# SAMV71_Xplained_Ultra_Connectors.net
KiCad netlist of a schematic drawn in Altium Designer
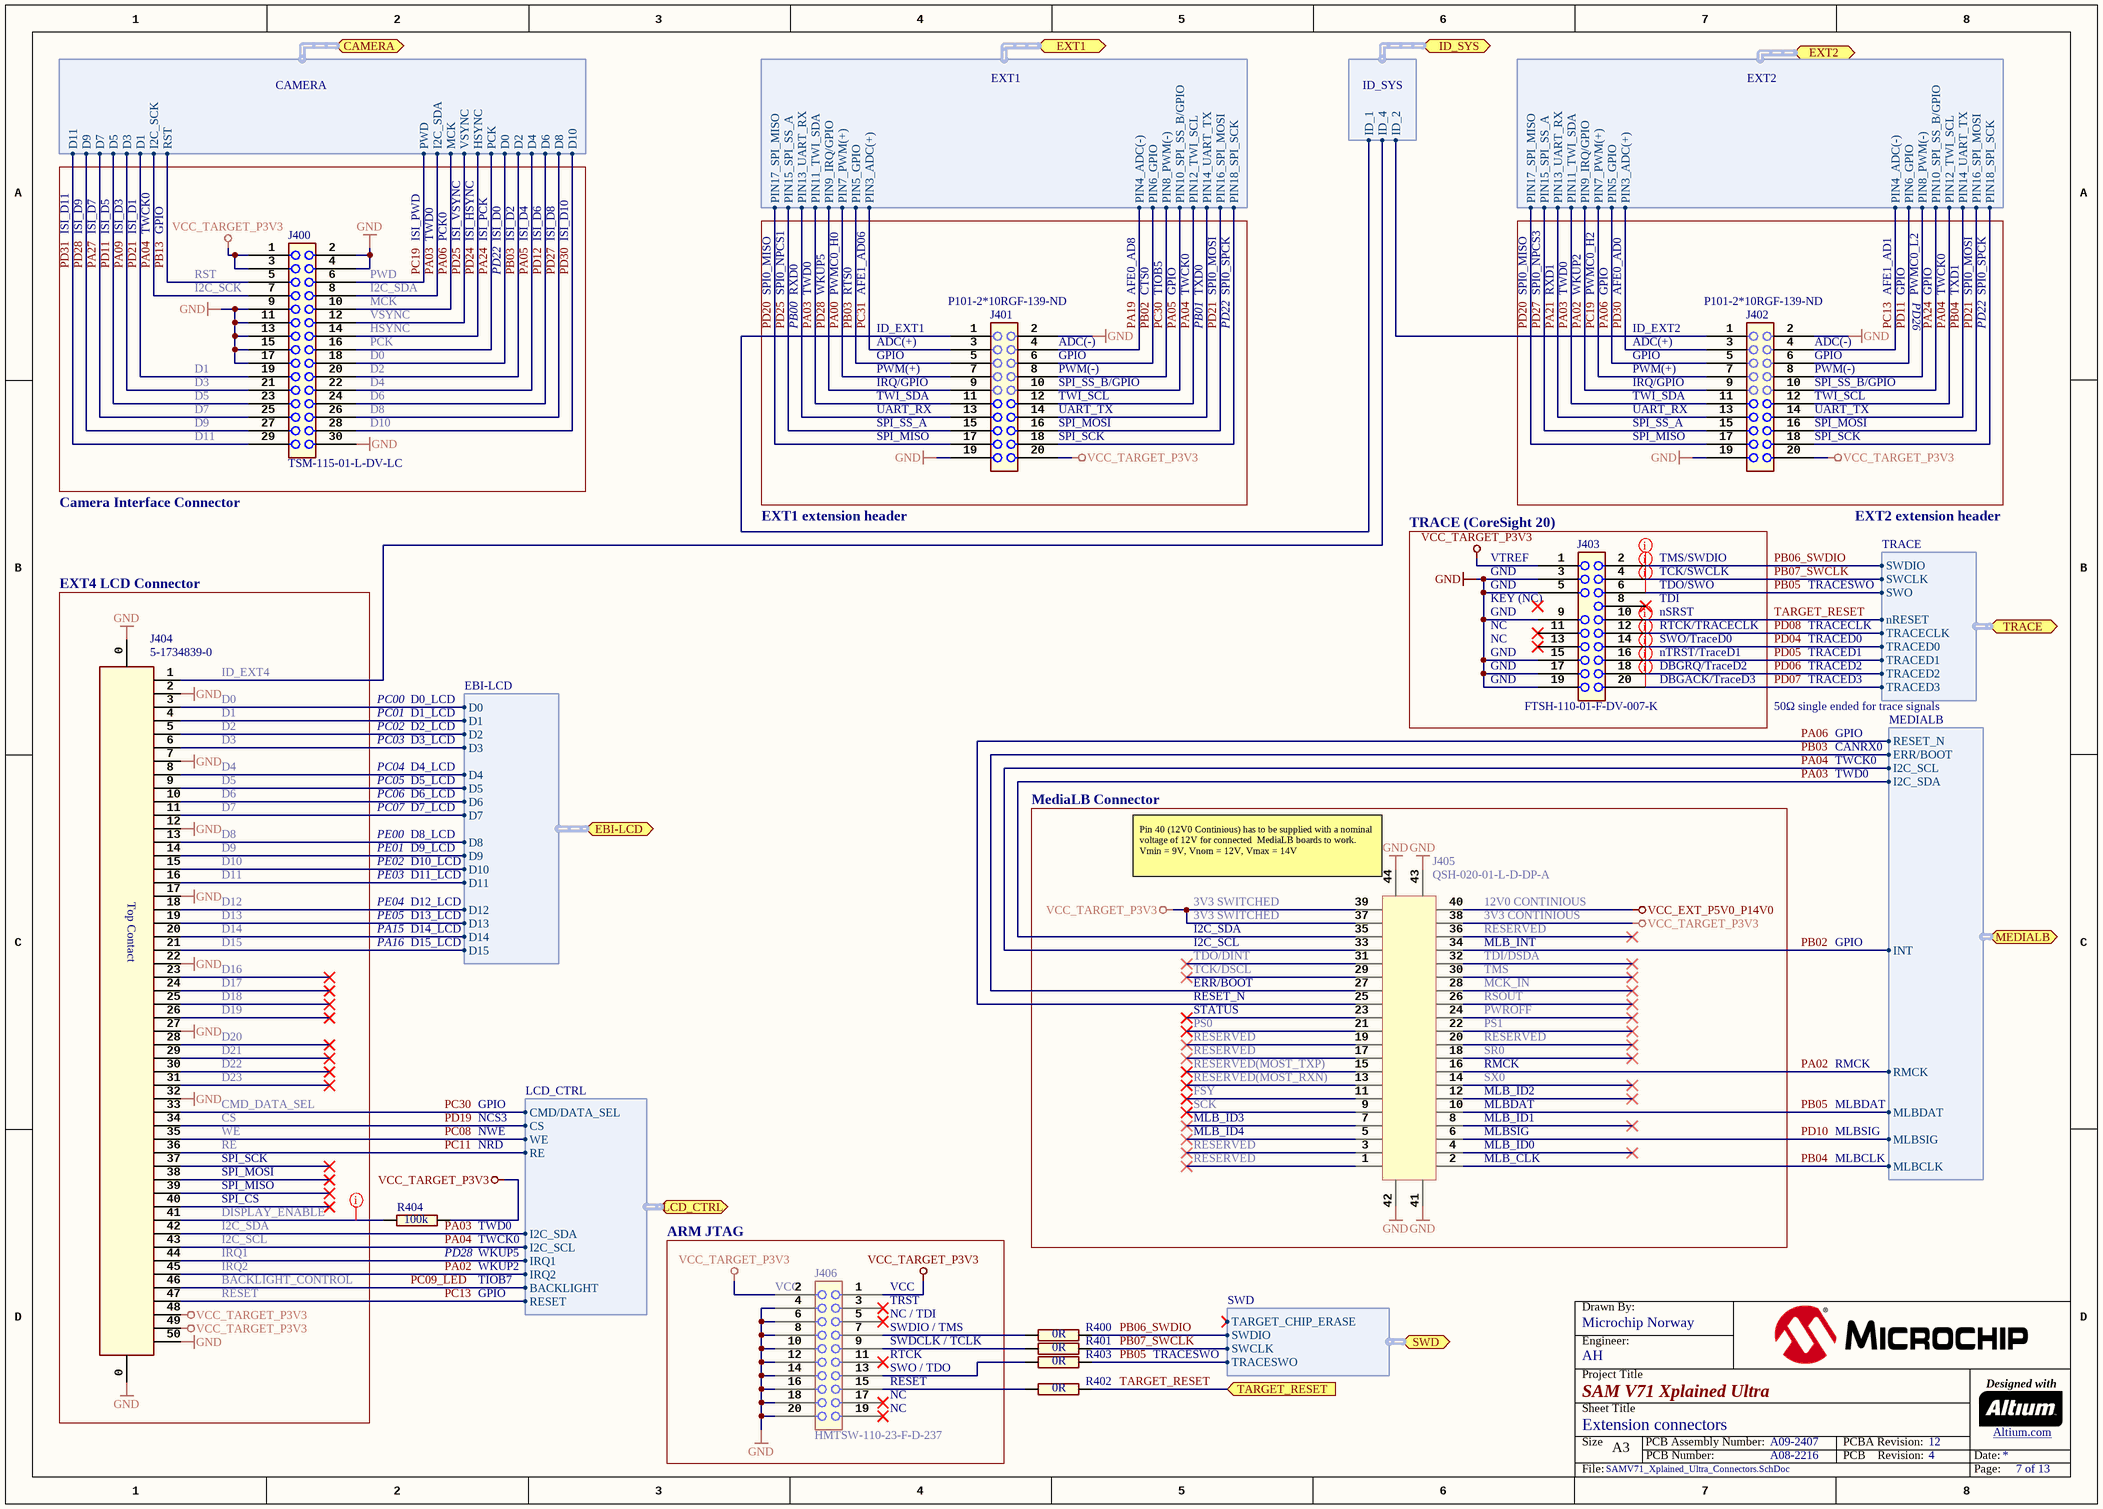
[diagram p0: SAMV71_Xplained_Ultra_Connectors.SchDoc]

(export (version "E")
  (design (tool "Eeschema 10.0.6"))
  (components
    (comp (ref "J400")
      (value "TSM-115-01-L-DV-LC")
      (footprint "AP8-00884")
      (description "Samtec TSM series, 2x15 pin header, straight, 2.54mm pitch SMD, locking leads.")
      (fields (field (name "MANUFACTURER") "SAMTEC"))
      (libsource (lib "AltiumDbLib") (part "HEADER 2x15"))
    )
    (comp (ref "J401")
      (value "P101-2*10RGF-139-ND")
      (footprint "AP8-00622")
      (description "Pin header, 2x10, Right Angle, 2.54mm, THM, Pin In Paste")
      (fields (field (name "MANUFACTURER") "Pro-data International Corp"))
      (libsource (lib "AltiumDbLib") (part "HEADER 2x10"))
    )
    (comp (ref "J402")
      (value "P101-2*10RGF-139-ND")
      (footprint "AP8-00622")
      (description "Pin header, 2x10, Right Angle, 2.54mm, THM, Pin In Paste")
      (fields (field (name "MANUFACTURER") "Pro-data International Corp"))
      (libsource (lib "AltiumDbLib") (part "HEADER 2x10"))
    )
    (comp (ref "J403")
      (value "FTSH-110-01-F-DV-007-K")
      (footprint "AP8-00910")
      (description "SAMTEC FTSH series 50-mil header, shrouded, pin 7 removed, SMD")
      (fields (field (name "MANUFACTURER") "SAMTEC"))
      (libsource (lib "AltiumDbLib") (part "FTSH-110-01-F-DV-007-K"))
    )
    (comp (ref "J404")
      (value "5-1734839-0")
      (footprint "AP8-00774")
      (description "50 pin FPC connector, e=0.5mm, single side contact (top).")
      (fields (field (name "MANUFACTURER") "TE Connectivity"))
      (libsource (lib "AltiumDbLib") (part "5-1734839-0"))
    )
    (comp (ref "J405")
      (value "QSH-020-01-L-D-DP-A")
      (footprint "AP8-00878")
      (description "SAMTEC 0.5mm, 20-pair, High-Speed Differential Pair Socket")
      (fields
        (field (name "MANUFACTURER") "SAMTEC")
        (field (name "Comment") "For SMSC MediaLB, \r\nMates with QTH-020-01-X-D-DP-XXX")
      )
      (libsource (lib "AltiumDbLib") (part "QSH-020-01-L-D-DP-A"))
    )
    (comp (ref "J406")
      (value "HMTSW-110-23-F-D-237")
      (footprint "AP8-00744")
      (description "2x10 pin header, 2.54mm pitch, Pin-in-Paste THM, 1mm hole")
      (fields (field (name "MANUFACTURER") "SAMTEC"))
      (libsource (lib "AltiumDbLib") (part "HEADER 2x10"))
    )
    (comp (ref "R400")
      (value "0R")
      (footprint "AP2-00000")
      (description "RES 0.0 OHM 1/16W 0402 SMD")
      (fields (field (name "TOLERANCE") "1 %") (field (name "MANUFACTURER") "(n/a)"))
      (libsource (lib "AltiumDbLib") (part "R2"))
    )
    (comp (ref "R401")
      (value "0R")
      (footprint "AP2-00000")
      (description "RES 0.0 OHM 1/16W 0402 SMD")
      (fields (field (name "TOLERANCE") "1 %") (field (name "MANUFACTURER") "(n/a)"))
      (libsource (lib "AltiumDbLib") (part "R2"))
    )
    (comp (ref "R402")
      (value "0R")
      (footprint "AP2-00000")
      (description "RES 0.0 OHM 1/16W 0402 SMD")
      (fields (field (name "TOLERANCE") "1 %") (field (name "MANUFACTURER") "(n/a)"))
      (libsource (lib "AltiumDbLib") (part "R2"))
    )
    (comp (ref "R403")
      (value "0R")
      (footprint "AP2-00000")
      (description "RES 0.0 OHM 1/16W 0402 SMD")
      (fields (field (name "TOLERANCE") "1 %") (field (name "MANUFACTURER") "(n/a)"))
      (libsource (lib "AltiumDbLib") (part "R2"))
    )
    (comp (ref "R404")
      (value "100k")
      (footprint "AP2-00011")
      (description "Thick film resistor, SMD 0402, 1/16W, 1%")
      (fields (field (name "TOLERANCE") "1 %") (field (name "MANUFACTURER") "ASJ"))
      (libsource (lib "") (part "R2_1"))
    )
  )
  (nets
    (net (code "10") (name "/D12") (class "Default")
      (node (ref "J404") (pin "18") (pinfunction "18_18") (pintype "passive"))
    )
    (net (code "11") (name "/D13") (class "Default")
      (node (ref "J404") (pin "19") (pinfunction "19_19") (pintype "passive"))
    )
    (net (code "12") (name "/D14") (class "Default")
      (node (ref "J404") (pin "20") (pinfunction "20_20") (pintype "passive"))
    )
    (net (code "13") (name "/D15") (class "Default")
      (node (ref "J404") (pin "21") (pinfunction "21_21") (pintype "passive"))
    )
    (net (code "14") (name "/ID_1") (class "Default")
      (node (ref "J401") (pin "1") (pinfunction "1_1") (pintype "passive"))
    )
    (net (code "15") (name "/ID_2") (class "Default")
      (node (ref "J402") (pin "1") (pinfunction "1_1") (pintype "passive"))
    )
    (net (code "16") (name "/ID_4") (class "Default")
      (node (ref "J404") (pin "1") (pinfunction "1_1") (pintype "passive"))
    )
    (net (code "17") (name "/IRQ1") (class "Default")
      (node (ref "J404") (pin "44") (pinfunction "44_44") (pintype "passive"))
    )
    (net (code "18") (name "/PA00") (class "Default")
      (node (ref "J401") (pin "7") (pinfunction "7_7") (pintype "passive"))
    )
    (net (code "19") (name "/PA02") (class "Default")
      (node (ref "J402") (pin "9") (pinfunction "9_9") (pintype "passive"))
      (node (ref "J404") (pin "45") (pinfunction "45_45") (pintype "passive"))
      (node (ref "J405") (pin "16") (pinfunction "16_16") (pintype "passive"))
    )
    (net (code "20") (name "/PA03") (class "Default")
      (node (ref "J400") (pin "8") (pinfunction "8_8") (pintype "passive"))
      (node (ref "J401") (pin "11") (pinfunction "11_11") (pintype "passive"))
      (node (ref "J402") (pin "11") (pinfunction "11_11") (pintype "passive"))
      (node (ref "J404") (pin "42") (pinfunction "42_42") (pintype "passive"))
      (node (ref "J405") (pin "35") (pinfunction "35_35") (pintype "passive"))
    )
    (net (code "21") (name "/PA04") (class "Default")
      (node (ref "J400") (pin "7") (pinfunction "7_7") (pintype "passive"))
      (node (ref "J401") (pin "12") (pinfunction "12_12") (pintype "passive"))
      (node (ref "J402") (pin "12") (pinfunction "12_12") (pintype "passive"))
      (node (ref "J404") (pin "43") (pinfunction "43_43") (pintype "passive"))
      (node (ref "J405") (pin "33") (pinfunction "33_33") (pintype "passive"))
    )
    (net (code "22") (name "/PA05") (class "Default")
      (node (ref "J400") (pin "22") (pinfunction "22_22") (pintype "passive"))
      (node (ref "J401") (pin "10") (pinfunction "10_10") (pintype "passive"))
    )
    (net (code "23") (name "/PA06") (class "Default")
      (node (ref "J400") (pin "10") (pinfunction "10_10") (pintype "passive"))
      (node (ref "J402") (pin "5") (pinfunction "5_5") (pintype "passive"))
      (node (ref "J405") (pin "25") (pinfunction "25_25") (pintype "passive"))
    )
    (net (code "24") (name "/PA09") (class "Default")
      (node (ref "J400") (pin "21") (pinfunction "21_21") (pintype "passive"))
    )
    (net (code "25") (name "/PA19") (class "Default")
      (node (ref "J401") (pin "4") (pinfunction "4_4") (pintype "passive"))
    )
    (net (code "26") (name "/PA21") (class "Default")
      (node (ref "J402") (pin "13") (pinfunction "13_13") (pintype "passive"))
    )
    (net (code "27") (name "/PA24") (class "Default")
      (node (ref "J400") (pin "16") (pinfunction "16_16") (pintype "passive"))
      (node (ref "J402") (pin "10") (pinfunction "10_10") (pintype "passive"))
    )
    (net (code "28") (name "/PA27") (class "Default")
      (node (ref "J400") (pin "25") (pinfunction "25_25") (pintype "passive"))
    )
    (net (code "29") (name "/PB02") (class "Default")
      (node (ref "J401") (pin "6") (pinfunction "6_6") (pintype "passive"))
      (node (ref "J405") (pin "34") (pinfunction "34_34") (pintype "passive"))
    )
    (net (code "30") (name "/PB03") (class "Default")
      (node (ref "J400") (pin "20") (pinfunction "20_20") (pintype "passive"))
      (node (ref "J401") (pin "5") (pinfunction "5_5") (pintype "passive"))
      (node (ref "J405") (pin "27") (pinfunction "27_27") (pintype "passive"))
    )
    (net (code "31") (name "/PB04") (class "Default")
      (node (ref "J402") (pin "14") (pinfunction "14_14") (pintype "passive"))
      (node (ref "J405") (pin "2") (pinfunction "2_2") (pintype "passive"))
    )
    (net (code "32") (name "/PB05") (class "Default")
      (node (ref "J403") (pin "6") (pinfunction "6_6") (pintype "passive"))
      (node (ref "J405") (pin "10") (pinfunction "10_10") (pintype "passive"))
      (node (ref "R403") (pin "2") (pinfunction "2_2") (pintype "passive"))
    )
    (net (code "33") (name "/PB06_SWDIO") (class "Default")
      (node (ref "J403") (pin "2") (pinfunction "2_2") (pintype "passive"))
      (node (ref "R400") (pin "2") (pinfunction "2_2") (pintype "passive"))
    )
    (net (code "34") (name "/PB07_SWCLK") (class "Default")
      (node (ref "J403") (pin "4") (pinfunction "4_4") (pintype "passive"))
      (node (ref "R401") (pin "2") (pinfunction "2_2") (pintype "passive"))
    )
    (net (code "35") (name "/PB13") (class "Default")
      (node (ref "J400") (pin "5") (pinfunction "5_5") (pintype "passive"))
    )
    (net (code "36") (name "/PC08") (class "Default")
      (node (ref "J404") (pin "35") (pinfunction "35_35") (pintype "passive"))
    )
    (net (code "37") (name "/PC09_LED") (class "Default")
      (node (ref "J404") (pin "46") (pinfunction "46_46") (pintype "passive"))
    )
    (net (code "38") (name "/PC11") (class "Default")
      (node (ref "J404") (pin "36") (pinfunction "36_36") (pintype "passive"))
    )
    (net (code "39") (name "/PC13") (class "Default")
      (node (ref "J402") (pin "4") (pinfunction "4_4") (pintype "passive"))
      (node (ref "J404") (pin "47") (pinfunction "47_47") (pintype "passive"))
    )
    (net (code "40") (name "/PC19") (class "Default")
      (node (ref "J400") (pin "6") (pinfunction "6_6") (pintype "passive"))
      (node (ref "J402") (pin "7") (pinfunction "7_7") (pintype "passive"))
    )
    (net (code "41") (name "/PC30") (class "Default")
      (node (ref "J401") (pin "8") (pinfunction "8_8") (pintype "passive"))
      (node (ref "J404") (pin "33") (pinfunction "33_33") (pintype "passive"))
    )
    (net (code "42") (name "/PC31") (class "Default")
      (node (ref "J401") (pin "3") (pinfunction "3_3") (pintype "passive"))
    )
    (net (code "43") (name "/PD04") (class "Default")
      (node (ref "J403") (pin "14") (pinfunction "14_14") (pintype "passive"))
    )
    (net (code "44") (name "/PD05") (class "Default")
      (node (ref "J403") (pin "16") (pinfunction "16_16") (pintype "passive"))
    )
    (net (code "45") (name "/PD06") (class "Default")
      (node (ref "J403") (pin "18") (pinfunction "18_18") (pintype "passive"))
    )
    (net (code "46") (name "/PD07") (class "Default")
      (node (ref "J403") (pin "20") (pinfunction "20_20") (pintype "passive"))
    )
    (net (code "47") (name "/PD08") (class "Default")
      (node (ref "J403") (pin "12") (pinfunction "12_12") (pintype "passive"))
    )
    (net (code "48") (name "/PD10") (class "Default")
      (node (ref "J405") (pin "6") (pinfunction "6_6") (pintype "passive"))
    )
    (net (code "49") (name "/PD11") (class "Default")
      (node (ref "J400") (pin "23") (pinfunction "23_23") (pintype "passive"))
      (node (ref "J402") (pin "6") (pinfunction "6_6") (pintype "passive"))
    )
    (net (code "50") (name "/PD12") (class "Default")
      (node (ref "J400") (pin "24") (pinfunction "24_24") (pintype "passive"))
    )
    (net (code "51") (name "/PD19") (class "Default")
      (node (ref "J404") (pin "34") (pinfunction "34_34") (pintype "passive"))
    )
    (net (code "52") (name "/PD20") (class "Default")
      (node (ref "J401") (pin "17") (pinfunction "17_17") (pintype "passive"))
      (node (ref "J402") (pin "17") (pinfunction "17_17") (pintype "passive"))
    )
    (net (code "53") (name "/PD21") (class "Default")
      (node (ref "J400") (pin "19") (pinfunction "19_19") (pintype "passive"))
      (node (ref "J401") (pin "16") (pinfunction "16_16") (pintype "passive"))
      (node (ref "J402") (pin "16") (pinfunction "16_16") (pintype "passive"))
    )
    (net (code "54") (name "/PD24") (class "Default")
      (node (ref "J400") (pin "14") (pinfunction "14_14") (pintype "passive"))
    )
    (net (code "55") (name "/PD25") (class "Default")
      (node (ref "J400") (pin "12") (pinfunction "12_12") (pintype "passive"))
      (node (ref "J401") (pin "15") (pinfunction "15_15") (pintype "passive"))
    )
    (net (code "56") (name "/PD27") (class "Default")
      (node (ref "J400") (pin "26") (pinfunction "26_26") (pintype "passive"))
      (node (ref "J402") (pin "15") (pinfunction "15_15") (pintype "passive"))
    )
    (net (code "57") (name "/PD28") (class "Default")
      (node (ref "J400") (pin "27") (pinfunction "27_27") (pintype "passive"))
      (node (ref "J401") (pin "9") (pinfunction "9_9") (pintype "passive"))
    )
    (net (code "58") (name "/PD30") (class "Default")
      (node (ref "J400") (pin "28") (pinfunction "28_28") (pintype "passive"))
      (node (ref "J402") (pin "3") (pinfunction "3_3") (pintype "passive"))
    )
    (net (code "59") (name "/PD31") (class "Default")
      (node (ref "J400") (pin "29") (pinfunction "29_29") (pintype "passive"))
    )
    (net (code "60") (name "/TARGET_RESET") (class "Default")
      (node (ref "J403") (pin "10") (pinfunction "10_10") (pintype "passive"))
      (node (ref "R402") (pin "2") (pinfunction "2_2") (pintype "passive"))
    )
    (net (code "70") (name "GND") (class "Default")
      (node (ref "J400") (pin "11") (pinfunction "11_11") (pintype "passive"))
      (node (ref "J400") (pin "13") (pinfunction "13_13") (pintype "passive"))
      (node (ref "J400") (pin "15") (pinfunction "15_15") (pintype "passive"))
      (node (ref "J400") (pin "17") (pinfunction "17_17") (pintype "passive"))
      (node (ref "J400") (pin "2") (pinfunction "2_2") (pintype "passive"))
      (node (ref "J400") (pin "30") (pinfunction "30_30") (pintype "passive"))
      (node (ref "J400") (pin "4") (pinfunction "4_4") (pintype "passive"))
      (node (ref "J400") (pin "9") (pinfunction "9_9") (pintype "passive"))
      (node (ref "J401") (pin "19") (pinfunction "19_19") (pintype "passive"))
      (node (ref "J401") (pin "2") (pinfunction "2_2") (pintype "passive"))
      (node (ref "J402") (pin "19") (pinfunction "19_19") (pintype "passive"))
      (node (ref "J402") (pin "2") (pinfunction "2_2") (pintype "passive"))
      (node (ref "J403") (pin "15") (pinfunction "15_15") (pintype "passive"))
      (node (ref "J403") (pin "17") (pinfunction "17_17") (pintype "passive"))
      (node (ref "J403") (pin "19") (pinfunction "19_19") (pintype "passive"))
      (node (ref "J403") (pin "3") (pinfunction "3_3") (pintype "passive"))
      (node (ref "J403") (pin "5") (pinfunction "5_5") (pintype "passive"))
      (node (ref "J403") (pin "9") (pinfunction "9_9") (pintype "passive"))
      (node (ref "J404") (pin "0") (pinfunction "1_0") (pintype "passive"))
      (node (ref "J404") (pin "12") (pinfunction "12_12") (pintype "passive"))
      (node (ref "J404") (pin "17") (pinfunction "17_17") (pintype "passive"))
      (node (ref "J404") (pin "2") (pinfunction "2_2") (pintype "passive"))
      (node (ref "J404") (pin "22") (pinfunction "22_22") (pintype "passive"))
      (node (ref "J404") (pin "27") (pinfunction "27_27") (pintype "passive"))
      (node (ref "J404") (pin "32") (pinfunction "32_32") (pintype "passive"))
      (node (ref "J404") (pin "50") (pinfunction "50_50") (pintype "passive"))
      (node (ref "J404") (pin "7") (pinfunction "7_7") (pintype "passive"))
      (node (ref "J405") (pin "41") (pinfunction "41_41") (pintype "passive"))
      (node (ref "J405") (pin "42") (pinfunction "42_42") (pintype "passive"))
      (node (ref "J405") (pin "43") (pinfunction "43_43") (pintype "passive"))
      (node (ref "J405") (pin "44") (pinfunction "44_44") (pintype "passive"))
      (node (ref "J406") (pin "10") (pinfunction "10_10") (pintype "passive"))
      (node (ref "J406") (pin "12") (pinfunction "12_12") (pintype "passive"))
      (node (ref "J406") (pin "14") (pinfunction "14_14") (pintype "passive"))
      (node (ref "J406") (pin "16") (pinfunction "16_16") (pintype "passive"))
      (node (ref "J406") (pin "18") (pinfunction "18_18") (pintype "passive"))
      (node (ref "J406") (pin "20") (pinfunction "20_20") (pintype "passive"))
      (node (ref "J406") (pin "4") (pinfunction "4_4") (pintype "passive"))
      (node (ref "J406") (pin "6") (pinfunction "6_6") (pintype "passive"))
      (node (ref "J406") (pin "8") (pinfunction "8_8") (pintype "passive"))
    )
    (net (code "71") (name "Net-(J404-Pad41)") (class "Default")
      (node (ref "J404") (pin "41") (pinfunction "41_41") (pintype "passive"))
      (node (ref "R404") (pin "2") (pinfunction "2_2") (pintype "passive"))
    )
    (net (code "72") (name "Net-(J406-Pad7)") (class "Default")
      (node (ref "J406") (pin "7") (pinfunction "7_7") (pintype "passive"))
      (node (ref "R400") (pin "1") (pinfunction "1_1") (pintype "passive"))
    )
    (net (code "73") (name "Net-(J406-Pad9)") (class "Default")
      (node (ref "J406") (pin "9") (pinfunction "9_9") (pintype "passive"))
      (node (ref "R401") (pin "1") (pinfunction "1_1") (pintype "passive"))
    )
    (net (code "74") (name "Net-(J406-Pad13)") (class "Default")
      (node (ref "J406") (pin "13") (pinfunction "13_13") (pintype "passive"))
      (node (ref "R403") (pin "1") (pinfunction "1_1") (pintype "passive"))
    )
    (net (code "75") (name "Net-(J406-Pad15)") (class "Default")
      (node (ref "J406") (pin "15") (pinfunction "15_15") (pintype "passive"))
      (node (ref "R402") (pin "1") (pinfunction "1_1") (pintype "passive"))
    )
    (net (code "76") (name "VCC_EXT_P5V0_P14V0") (class "Default")
      (node (ref "J405") (pin "40") (pinfunction "40_40") (pintype "passive"))
    )
    (net (code "77") (name "VCC_TARGET_P3V3") (class "Default")
      (node (ref "J400") (pin "1") (pinfunction "1_1") (pintype "passive"))
      (node (ref "J400") (pin "3") (pinfunction "3_3") (pintype "passive"))
      (node (ref "J401") (pin "20") (pinfunction "20_20") (pintype "passive"))
      (node (ref "J402") (pin "20") (pinfunction "20_20") (pintype "passive"))
      (node (ref "J403") (pin "1") (pinfunction "1_1") (pintype "passive"))
      (node (ref "J404") (pin "48") (pinfunction "48_48") (pintype "passive"))
      (node (ref "J404") (pin "49") (pinfunction "49_49") (pintype "passive"))
      (node (ref "J405") (pin "37") (pinfunction "37_37") (pintype "passive"))
      (node (ref "J405") (pin "38") (pinfunction "38_38") (pintype "passive"))
      (node (ref "J405") (pin "39") (pinfunction "39_39") (pintype "passive"))
      (node (ref "J406") (pin "1") (pinfunction "1_1") (pintype "passive"))
      (node (ref "J406") (pin "2") (pinfunction "2_2") (pintype "passive"))
      (node (ref "R404") (pin "1") (pinfunction "1_1") (pintype "passive"))
    )
    (net (code "78") (name "unconnected-(J400-Pad18)") (class "Default")
      (node (ref "J400") (pin "18") (pinfunction "18_18") (pintype "passive"))
    )
    (net (code "79") (name "unconnected-(J401-Pad13)") (class "Default")
      (node (ref "J401") (pin "13") (pinfunction "13_13") (pintype "passive"))
    )
    (net (code "80") (name "unconnected-(J401-Pad14)") (class "Default")
      (node (ref "J401") (pin "14") (pinfunction "14_14") (pintype "passive"))
    )
    (net (code "81") (name "unconnected-(J401-Pad18)") (class "Default")
      (node (ref "J401") (pin "18") (pinfunction "18_18") (pintype "passive"))
    )
    (net (code "82") (name "unconnected-(J402-Pad8)") (class "Default")
      (node (ref "J402") (pin "8") (pinfunction "8_8") (pintype "passive"))
    )
    (net (code "83") (name "unconnected-(J402-Pad18)") (class "Default")
      (node (ref "J402") (pin "18") (pinfunction "18_18") (pintype "passive"))
    )
    (net (code "84") (name "unconnected-(J403-Pad8)") (class "Default")
      (node (ref "J403") (pin "8") (pinfunction "8_8") (pintype "passive+no_connect"))
    )
    (net (code "85") (name "unconnected-(J403-Pad11)") (class "Default")
      (node (ref "J403") (pin "11") (pinfunction "11_11") (pintype "passive+no_connect"))
    )
    (net (code "86") (name "unconnected-(J403-Pad13)") (class "Default")
      (node (ref "J403") (pin "13") (pinfunction "13_13") (pintype "passive+no_connect"))
    )
    (net (code "87") (name "unconnected-(J404-Pad3)") (class "Default")
      (node (ref "J404") (pin "3") (pinfunction "3_3") (pintype "passive"))
    )
    (net (code "88") (name "unconnected-(J404-Pad4)") (class "Default")
      (node (ref "J404") (pin "4") (pinfunction "4_4") (pintype "passive"))
    )
    (net (code "89") (name "unconnected-(J404-Pad5)") (class "Default")
      (node (ref "J404") (pin "5") (pinfunction "5_5") (pintype "passive"))
    )
    (net (code "90") (name "unconnected-(J404-Pad6)") (class "Default")
      (node (ref "J404") (pin "6") (pinfunction "6_6") (pintype "passive"))
    )
    (net (code "91") (name "unconnected-(J404-Pad8)") (class "Default")
      (node (ref "J404") (pin "8") (pinfunction "8_8") (pintype "passive"))
    )
    (net (code "92") (name "unconnected-(J404-Pad9)") (class "Default")
      (node (ref "J404") (pin "9") (pinfunction "9_9") (pintype "passive"))
    )
    (net (code "93") (name "unconnected-(J404-Pad10)") (class "Default")
      (node (ref "J404") (pin "10") (pinfunction "10_10") (pintype "passive"))
    )
    (net (code "94") (name "unconnected-(J404-Pad11)") (class "Default")
      (node (ref "J404") (pin "11") (pinfunction "11_11") (pintype "passive"))
    )
    (net (code "95") (name "unconnected-(J404-Pad13)") (class "Default")
      (node (ref "J404") (pin "13") (pinfunction "13_13") (pintype "passive"))
    )
    (net (code "96") (name "unconnected-(J404-Pad14)") (class "Default")
      (node (ref "J404") (pin "14") (pinfunction "14_14") (pintype "passive"))
    )
    (net (code "97") (name "unconnected-(J404-Pad15)") (class "Default")
      (node (ref "J404") (pin "15") (pinfunction "15_15") (pintype "passive"))
    )
    (net (code "98") (name "unconnected-(J404-Pad16)") (class "Default")
      (node (ref "J404") (pin "16") (pinfunction "16_16") (pintype "passive"))
    )
    (net (code "99") (name "unconnected-(J404-Pad23)") (class "Default")
      (node (ref "J404") (pin "23") (pinfunction "23_23") (pintype "passive+no_connect"))
    )
    (net (code "100") (name "unconnected-(J404-Pad24)") (class "Default")
      (node (ref "J404") (pin "24") (pinfunction "24_24") (pintype "passive+no_connect"))
    )
    (net (code "101") (name "unconnected-(J404-Pad25)") (class "Default")
      (node (ref "J404") (pin "25") (pinfunction "25_25") (pintype "passive+no_connect"))
    )
    (net (code "102") (name "unconnected-(J404-Pad26)") (class "Default")
      (node (ref "J404") (pin "26") (pinfunction "26_26") (pintype "passive+no_connect"))
    )
    (net (code "103") (name "unconnected-(J404-Pad28)") (class "Default")
      (node (ref "J404") (pin "28") (pinfunction "28_28") (pintype "passive+no_connect"))
    )
    (net (code "104") (name "unconnected-(J404-Pad29)") (class "Default")
      (node (ref "J404") (pin "29") (pinfunction "29_29") (pintype "passive+no_connect"))
    )
    (net (code "105") (name "unconnected-(J404-Pad30)") (class "Default")
      (node (ref "J404") (pin "30") (pinfunction "30_30") (pintype "passive+no_connect"))
    )
    (net (code "106") (name "unconnected-(J404-Pad31)") (class "Default")
      (node (ref "J404") (pin "31") (pinfunction "31_31") (pintype "passive+no_connect"))
    )
    (net (code "107") (name "unconnected-(J404-Pad37)") (class "Default")
      (node (ref "J404") (pin "37") (pinfunction "37_37") (pintype "passive+no_connect"))
    )
    (net (code "108") (name "unconnected-(J404-Pad38)") (class "Default")
      (node (ref "J404") (pin "38") (pinfunction "38_38") (pintype "passive+no_connect"))
    )
    (net (code "109") (name "unconnected-(J404-Pad39)") (class "Default")
      (node (ref "J404") (pin "39") (pinfunction "39_39") (pintype "passive+no_connect"))
    )
    (net (code "110") (name "unconnected-(J404-Pad40)") (class "Default")
      (node (ref "J404") (pin "40") (pinfunction "40_40") (pintype "passive+no_connect"))
    )
    (net (code "111") (name "unconnected-(J405-Pad1)") (class "Default")
      (node (ref "J405") (pin "1") (pinfunction "1_1") (pintype "passive+no_connect"))
    )
    (net (code "112") (name "unconnected-(J405-Pad3)") (class "Default")
      (node (ref "J405") (pin "3") (pinfunction "3_3") (pintype "passive+no_connect"))
    )
    (net (code "113") (name "unconnected-(J405-Pad4)") (class "Default")
      (node (ref "J405") (pin "4") (pinfunction "4_4") (pintype "passive+no_connect"))
    )
    (net (code "114") (name "unconnected-(J405-Pad5)") (class "Default")
      (node (ref "J405") (pin "5") (pinfunction "5_5") (pintype "passive+no_connect"))
    )
    (net (code "115") (name "unconnected-(J405-Pad7)") (class "Default")
      (node (ref "J405") (pin "7") (pinfunction "7_7") (pintype "passive+no_connect"))
    )
    (net (code "116") (name "unconnected-(J405-Pad8)") (class "Default")
      (node (ref "J405") (pin "8") (pinfunction "8_8") (pintype "passive+no_connect"))
    )
    (net (code "117") (name "unconnected-(J405-Pad9)") (class "Default")
      (node (ref "J405") (pin "9") (pinfunction "9_9") (pintype "passive+no_connect"))
    )
    (net (code "118") (name "unconnected-(J405-Pad11)") (class "Default")
      (node (ref "J405") (pin "11") (pinfunction "11_11") (pintype "passive+no_connect"))
    )
    (net (code "119") (name "unconnected-(J405-Pad12)") (class "Default")
      (node (ref "J405") (pin "12") (pinfunction "12_12") (pintype "passive+no_connect"))
    )
    (net (code "120") (name "unconnected-(J405-Pad13)") (class "Default")
      (node (ref "J405") (pin "13") (pinfunction "13_13") (pintype "passive+no_connect"))
    )
    (net (code "121") (name "unconnected-(J405-Pad14)") (class "Default")
      (node (ref "J405") (pin "14") (pinfunction "14_14") (pintype "passive+no_connect"))
    )
    (net (code "122") (name "unconnected-(J405-Pad15)") (class "Default")
      (node (ref "J405") (pin "15") (pinfunction "15_15") (pintype "passive+no_connect"))
    )
    (net (code "123") (name "unconnected-(J405-Pad17)") (class "Default")
      (node (ref "J405") (pin "17") (pinfunction "17_17") (pintype "passive+no_connect"))
    )
    (net (code "124") (name "unconnected-(J405-Pad18)") (class "Default")
      (node (ref "J405") (pin "18") (pinfunction "18_18") (pintype "passive+no_connect"))
    )
    (net (code "125") (name "unconnected-(J405-Pad19)") (class "Default")
      (node (ref "J405") (pin "19") (pinfunction "19_19") (pintype "passive+no_connect"))
    )
    (net (code "126") (name "unconnected-(J405-Pad20)") (class "Default")
      (node (ref "J405") (pin "20") (pinfunction "20_20") (pintype "passive+no_connect"))
    )
    (net (code "127") (name "unconnected-(J405-Pad21)") (class "Default")
      (node (ref "J405") (pin "21") (pinfunction "21_21") (pintype "passive+no_connect"))
    )
    (net (code "128") (name "unconnected-(J405-Pad22)") (class "Default")
      (node (ref "J405") (pin "22") (pinfunction "22_22") (pintype "passive+no_connect"))
    )
    (net (code "129") (name "unconnected-(J405-Pad23)") (class "Default")
      (node (ref "J405") (pin "23") (pinfunction "23_23") (pintype "passive+no_connect"))
    )
    (net (code "130") (name "unconnected-(J405-Pad24)") (class "Default")
      (node (ref "J405") (pin "24") (pinfunction "24_24") (pintype "passive+no_connect"))
    )
    (net (code "131") (name "unconnected-(J405-Pad26)") (class "Default")
      (node (ref "J405") (pin "26") (pinfunction "26_26") (pintype "passive+no_connect"))
    )
    (net (code "132") (name "unconnected-(J405-Pad28)") (class "Default")
      (node (ref "J405") (pin "28") (pinfunction "28_28") (pintype "passive+no_connect"))
    )
    (net (code "133") (name "unconnected-(J405-Pad29)") (class "Default")
      (node (ref "J405") (pin "29") (pinfunction "29_29") (pintype "passive+no_connect"))
    )
    (net (code "134") (name "unconnected-(J405-Pad30)") (class "Default")
      (node (ref "J405") (pin "30") (pinfunction "30_30") (pintype "passive+no_connect"))
    )
    (net (code "135") (name "unconnected-(J405-Pad31)") (class "Default")
      (node (ref "J405") (pin "31") (pinfunction "31_31") (pintype "passive+no_connect"))
    )
    (net (code "136") (name "unconnected-(J405-Pad32)") (class "Default")
      (node (ref "J405") (pin "32") (pinfunction "32_32") (pintype "passive+no_connect"))
    )
    (net (code "137") (name "unconnected-(J405-Pad36)") (class "Default")
      (node (ref "J405") (pin "36") (pinfunction "36_36") (pintype "passive+no_connect"))
    )
    (net (code "138") (name "unconnected-(J406-Pad3)") (class "Default")
      (node (ref "J406") (pin "3") (pinfunction "3_3") (pintype "passive+no_connect"))
    )
    (net (code "139") (name "unconnected-(J406-Pad5)") (class "Default")
      (node (ref "J406") (pin "5") (pinfunction "5_5") (pintype "passive+no_connect"))
    )
    (net (code "140") (name "unconnected-(J406-Pad11)") (class "Default")
      (node (ref "J406") (pin "11") (pinfunction "11_11") (pintype "passive+no_connect"))
    )
    (net (code "141") (name "unconnected-(J406-Pad17)") (class "Default")
      (node (ref "J406") (pin "17") (pinfunction "17_17") (pintype "passive+no_connect"))
    )
    (net (code "142") (name "unconnected-(J406-Pad19)") (class "Default")
      (node (ref "J406") (pin "19") (pinfunction "19_19") (pintype "passive+no_connect"))
    )
  )
)
